# QSPIFlash.net
KiCad netlist of a schematic drawn in Altium Designer
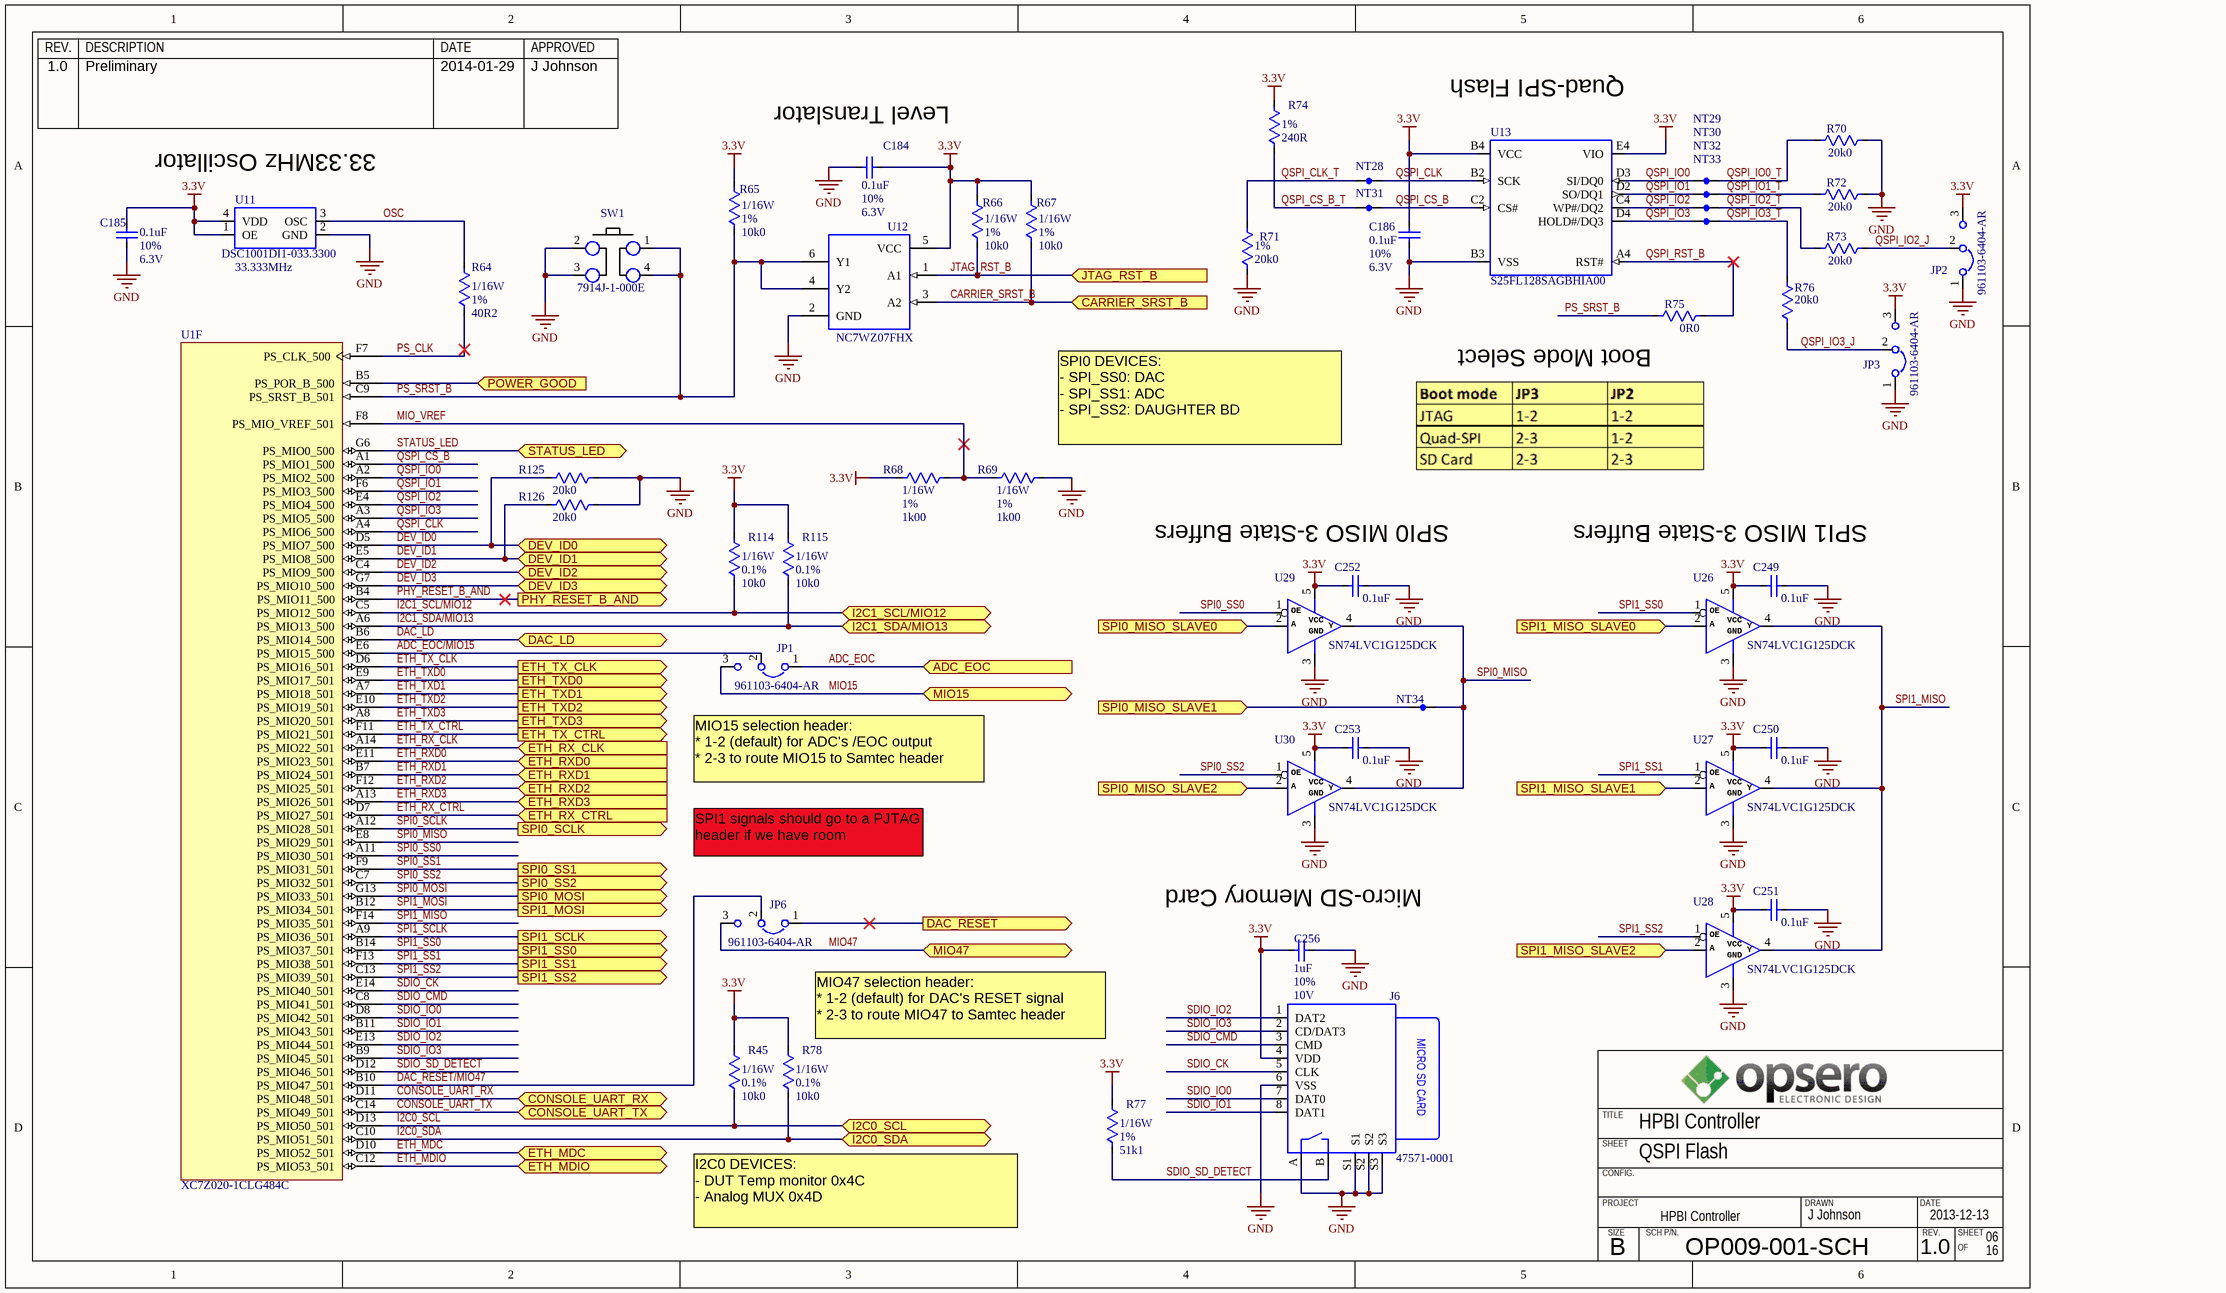
[diagram p0: QSPIFlash.SchDoc]

(export (version "E")
  (design (tool "Eeschema 10.0.6"))
  (components
    (comp (ref "C184")
      (value "0.1uF")
      (footprint "CAPC0603X33N")
      (description "Capacitor ceramic, X5R, 0.1uF, 6.3V, 10%, -55 to +125 C, EIA0201")
      (fields
        (field (name "TOLERANCE") "10%")
        (field (name "VOLTAGE") "6.3V")
        (field (name "Comment") "CAPACITOR_NP_TYPE1")
      )
      (libsource (lib "parts") (part "CAPACITOR_NP_TYPE1"))
    )
    (comp (ref "C185")
      (value "0.1uF")
      (footprint "CAPC0603X33N")
      (description "Capacitor ceramic, X5R, 0.1uF, 6.3V, 10%, -55 to +125 C, EIA0201")
      (fields
        (field (name "TOLERANCE") "10%")
        (field (name "VOLTAGE") "6.3V")
        (field (name "Comment") "CAPACITOR_NP_TYPE1")
      )
      (libsource (lib "parts") (part "CAPACITOR_NP_TYPE1"))
    )
    (comp (ref "C186")
      (value "0.1uF")
      (footprint "CAPC0603X33N")
      (description "Capacitor ceramic, X5R, 0.1uF, 6.3V, 10%, -55 to +125 C, EIA0201")
      (fields
        (field (name "TOLERANCE") "10%")
        (field (name "VOLTAGE") "6.3V")
        (field (name "Comment") "CAPACITOR_NP_TYPE1")
      )
      (libsource (lib "parts") (part "CAPACITOR_NP_TYPE1"))
    )
    (comp (ref "C249")
      (value "0.1uF")
      (footprint "CAPC0603X33N")
      (description "Capacitor ceramic, X5R, 0.1uF, 6.3V, 10%, -55 to +125 C, EIA0201")
      (fields (field (name "TOLERANCE") "10%") (field (name "VOLTAGE") "6.3V"))
      (libsource (lib "parts") (part "CAPACITOR_NP_TYPE1"))
    )
    (comp (ref "C250")
      (value "0.1uF")
      (footprint "CAPC0603X33N")
      (description "Capacitor ceramic, X5R, 0.1uF, 6.3V, 10%, -55 to +125 C, EIA0201")
      (fields (field (name "TOLERANCE") "10%") (field (name "VOLTAGE") "6.3V"))
      (libsource (lib "parts") (part "CAPACITOR_NP_TYPE1"))
    )
    (comp (ref "C251")
      (value "0.1uF")
      (footprint "CAPC0603X33N")
      (description "Capacitor ceramic, X5R, 0.1uF, 6.3V, 10%, -55 to +125 C, EIA0201")
      (fields (field (name "TOLERANCE") "10%") (field (name "VOLTAGE") "6.3V"))
      (libsource (lib "parts") (part "CAPACITOR_NP_TYPE1"))
    )
    (comp (ref "C252")
      (value "0.1uF")
      (footprint "CAPC0603X33N")
      (description "Capacitor ceramic, X5R, 0.1uF, 6.3V, 10%, -55 to +125 C, EIA0201")
      (fields (field (name "TOLERANCE") "10%") (field (name "VOLTAGE") "6.3V"))
      (libsource (lib "parts") (part "CAPACITOR_NP_TYPE1"))
    )
    (comp (ref "C253")
      (value "0.1uF")
      (footprint "CAPC0603X33N")
      (description "Capacitor ceramic, X5R, 0.1uF, 6.3V, 10%, -55 to +125 C, EIA0201")
      (fields (field (name "TOLERANCE") "10%") (field (name "VOLTAGE") "6.3V"))
      (libsource (lib "parts") (part "CAPACITOR_NP_TYPE1"))
    )
    (comp (ref "C256")
      (value "1uF")
      (footprint "CAPC1005X33N")
      (description "Capacitor ceramic, X5R, 1uF, 10V, 10%, -55 to +85 C, EIA0402")
      (fields
        (field (name "TOLERANCE") "10%")
        (field (name "VOLTAGE") "10V")
        (field (name "Comment") "CAPACITOR_NP_TYPE1")
      )
      (libsource (lib "parts") (part "CAPACITOR_NP_TYPE1"))
    )
    (comp (ref "J6")
      (value "SD_MICRO_DET1")
      (footprint "47571-0001")
      (description "MicroSD Card Header with Detect, 9 pin, RA, 1.10 mm, SMT, -40 to +85C")
      (fields
        (field (name "POWER") "Pow")
        (field (name "VOLTAGE") "Vol")
        (field (name "MFG PART NUMBER 1") "47571-0001")
      )
      (libsource (lib "parts") (part "SD_MICRO_DET1"))
    )
    (comp (ref "JP1")
      (value "JP_HDR3x1_DEF1")
      (footprint "JMPR3P254_SHUNT12")
      (description "Jumper Header .100'', 3-pin, Default position 1-2, TH")
      (fields
        (field (name "POWER") "Pow")
        (field (name "VOLTAGE") "Vol")
        (field (name "MFG PART NUMBER 1") "961103-6404-AR")
      )
      (libsource (lib "parts") (part "JP_HDR3x1_DEF1"))
    )
    (comp (ref "JP2")
      (value "JP_HDR3x1_DEF1")
      (footprint "JMPR3P254_SHUNT12")
      (description "Jumper Header .100'', 3-pin, Default position 1-2, TH")
      (fields
        (field (name "POWER") "Pow")
        (field (name "VOLTAGE") "Vol")
        (field (name "MFG PART NUMBER 1") "961103-6404-AR")
      )
      (libsource (lib "") (part "JP_HDR3x1_DEF1_1"))
    )
    (comp (ref "JP3")
      (value "JP_HDR3x1_DEF1")
      (footprint "JMPR3P254_SHUNT12")
      (description "Jumper Header .100'', 3-pin, Default position 1-2, TH")
      (fields
        (field (name "POWER") "Pow")
        (field (name "VOLTAGE") "Vol")
        (field (name "MFG PART NUMBER 1") "961103-6404-AR")
      )
      (libsource (lib "") (part "JP_HDR3x1_DEF1_1"))
    )
    (comp (ref "JP6")
      (value "JP_HDR3x1_DEF1")
      (footprint "JMPR3P254_SHUNT12")
      (description "Jumper Header .100'', 3-pin, Default position 1-2, TH")
      (fields
        (field (name "POWER") "Pow")
        (field (name "VOLTAGE") "Vol")
        (field (name "MFG PART NUMBER 1") "961103-6404-AR")
      )
      (libsource (lib "parts") (part "JP_HDR3x1_DEF1"))
    )
    (comp (ref "NT28")
      (value "NET_TIE_1X1")
      (footprint "NET_TIE_1X1")
      (description "Net Tie 1 to 1")
      (libsource (lib "parts") (part "NET_TIE_1X1"))
    )
    (comp (ref "NT29")
      (value "NET_TIE_1X1")
      (footprint "NET_TIE_1X1")
      (description "Net Tie 1 to 1")
      (libsource (lib "parts") (part "NET_TIE_1X1"))
    )
    (comp (ref "NT30")
      (value "NET_TIE_1X1")
      (footprint "NET_TIE_1X1")
      (description "Net Tie 1 to 1")
      (libsource (lib "parts") (part "NET_TIE_1X1"))
    )
    (comp (ref "NT31")
      (value "NET_TIE_1X1")
      (footprint "NET_TIE_1X1")
      (description "Net Tie 1 to 1")
      (libsource (lib "parts") (part "NET_TIE_1X1"))
    )
    (comp (ref "NT32")
      (value "NET_TIE_1X1")
      (footprint "NET_TIE_1X1")
      (description "Net Tie 1 to 1")
      (libsource (lib "parts") (part "NET_TIE_1X1"))
    )
    (comp (ref "NT33")
      (value "NET_TIE_1X1")
      (footprint "NET_TIE_1X1")
      (description "Net Tie 1 to 1")
      (libsource (lib "parts") (part "NET_TIE_1X1"))
    )
    (comp (ref "NT34")
      (value "NET_TIE_1X1")
      (footprint "NET_TIE_1X1")
      (description "Net Tie 1 to 1")
      (libsource (lib "parts") (part "NET_TIE_1X1"))
    )
    (comp (ref "R45")
      (value "10k0")
      (footprint "RESC1005X33N")
      (description "Resistor, 10k0, 1/16W, 0.1%, -50 to +155 C, EIA0402")
      (fields (field (name "VOLTAGE") "50V") (field (name "POWER") "1/16W") (field (name "TOLERANCE") "0.1%"))
      (libsource (lib "parts") (part "RESISTOR_TYPE1"))
    )
    (comp (ref "R64")
      (value "40R2")
      (footprint "RESC1005X33N")
      (description "Resistor, 40R2, 1/16W, 1%, -50 to +155 C, EIA0402, EIA(M)1005")
      (fields (field (name "VOLTAGE") "50V") (field (name "POWER") "1/16W") (field (name "TOLERANCE") "1%"))
      (libsource (lib "parts") (part "RESISTOR_TYPE1"))
    )
    (comp (ref "R65")
      (value "10k0")
      (footprint "RESC1005X33N")
      (description "Resistor, 10k0, 1/16W, 1%, -55 to +155 C, EIA0402")
      (fields (field (name "VOLTAGE") "50V") (field (name "POWER") "1/16W") (field (name "TOLERANCE") "1%"))
      (libsource (lib "parts") (part "RESISTOR_TYPE1"))
    )
    (comp (ref "R66")
      (value "10k0")
      (footprint "RESC1005X33N")
      (description "Resistor, 10k0, 1/16W, 1%, -55 to +155 C, EIA0402")
      (fields (field (name "VOLTAGE") "50V") (field (name "POWER") "1/16W") (field (name "TOLERANCE") "1%"))
      (libsource (lib "parts") (part "RESISTOR_TYPE1"))
    )
    (comp (ref "R67")
      (value "10k0")
      (footprint "RESC1005X33N")
      (description "Resistor, 10k0, 1/16W, 1%, -55 to +155 C, EIA0402")
      (fields (field (name "VOLTAGE") "50V") (field (name "POWER") "1/16W") (field (name "TOLERANCE") "1%"))
      (libsource (lib "parts") (part "RESISTOR_TYPE1"))
    )
    (comp (ref "R68")
      (value "1k00")
      (footprint "RESC1005X33N")
      (description "Resistor, 1k00, 1/16W, 1%, -55 to +155 C, EIA0402")
      (fields (field (name "VOLTAGE") "50V") (field (name "POWER") "1/16W") (field (name "TOLERANCE") "1%"))
      (libsource (lib "parts") (part "RESISTOR_TYPE1"))
    )
    (comp (ref "R69")
      (value "1k00")
      (footprint "RESC1005X33N")
      (description "Resistor, 1k00, 1/16W, 1%, -55 to +155 C, EIA0402")
      (fields (field (name "VOLTAGE") "50V") (field (name "POWER") "1/16W") (field (name "TOLERANCE") "1%"))
      (libsource (lib "parts") (part "RESISTOR_TYPE1"))
    )
    (comp (ref "R70")
      (value "20k0")
      (footprint "RESC1005X33N")
      (description "Resistor, 20k0, 1/16W, 1%, -50 to +155 C, EIA0402, EIA(M)1005")
      (fields (field (name "VOLTAGE") "50V") (field (name "POWER") "1/16W"))
      (libsource (lib "parts") (part "RESISTOR_TYPE1"))
    )
    (comp (ref "R71")
      (value "20k0")
      (footprint "RESC1005X33N")
      (description "Resistor, 20k0, 1/16W, 1%, -50 to +155 C, EIA0402, EIA(M)1005")
      (fields (field (name "VOLTAGE") "50V") (field (name "POWER") "1/16W") (field (name "TOLERANCE") "1%"))
      (libsource (lib "parts") (part "RESISTOR_TYPE1"))
    )
    (comp (ref "R72")
      (value "20k0")
      (footprint "RESC1005X33N")
      (description "Resistor, 20k0, 1/16W, 1%, -50 to +155 C, EIA0402, EIA(M)1005")
      (fields (field (name "VOLTAGE") "50V") (field (name "POWER") "1/16W"))
      (libsource (lib "parts") (part "RESISTOR_TYPE1"))
    )
    (comp (ref "R73")
      (value "20k0")
      (footprint "RESC1005X33N")
      (description "Resistor, 20k0, 1/16W, 1%, -50 to +155 C, EIA0402, EIA(M)1005")
      (fields (field (name "VOLTAGE") "50V") (field (name "POWER") "1/16W"))
      (libsource (lib "parts") (part "RESISTOR_TYPE1"))
    )
    (comp (ref "R74")
      (value "240R")
      (footprint "RESC1005X33N")
      (description "Resistor, 240R, 1/16W, 1%, -50 to +155 C, EIA0402, EIA(M)1005")
      (fields (field (name "VOLTAGE") "50V") (field (name "POWER") "1/16W") (field (name "TOLERANCE") "1%"))
      (libsource (lib "parts") (part "RESISTOR_TYPE1"))
    )
    (comp (ref "R75")
      (value "0R0")
      (footprint "RESC1005X33N")
      (description "Resistor, 0R0, 1/16W, 1%, -50 to +155 C, EIA0402, EIA(M)1005")
      (fields (field (name "VOLTAGE") "50V") (field (name "POWER") "1/16W"))
      (libsource (lib "parts") (part "RESISTOR_TYPE1"))
    )
    (comp (ref "R76")
      (value "20k0")
      (footprint "RESC1005X33N")
      (description "Resistor, 20k0, 1/16W, 1%, -50 to +155 C, EIA0402, EIA(M)1005")
      (fields (field (name "VOLTAGE") "50V") (field (name "POWER") "1/16W"))
      (libsource (lib "parts") (part "RESISTOR_TYPE1"))
    )
    (comp (ref "R77")
      (value "51k1")
      (footprint "RESC1005X33N")
      (description "Resistor, 51k1, 1/16W, 1%, -50 to +155 C, EIA0402, EIA(M)1005")
      (fields (field (name "VOLTAGE") "50V") (field (name "POWER") "1/16W") (field (name "TOLERANCE") "1%"))
      (libsource (lib "parts") (part "RESISTOR_TYPE1"))
    )
    (comp (ref "R78")
      (value "10k0")
      (footprint "RESC1005X33N")
      (description "Resistor, 10k0, 1/16W, 0.1%, -50 to +155 C, EIA0402")
      (fields (field (name "VOLTAGE") "50V") (field (name "POWER") "1/16W") (field (name "TOLERANCE") "0.1%"))
      (libsource (lib "parts") (part "RESISTOR_TYPE1"))
    )
    (comp (ref "R114")
      (value "10k0")
      (footprint "RESC1005X33N")
      (description "Resistor, 10k0, 1/16W, 0.1%, -50 to +155 C, EIA0402")
      (fields (field (name "VOLTAGE") "50V") (field (name "POWER") "1/16W") (field (name "TOLERANCE") "0.1%"))
      (libsource (lib "parts") (part "RESISTOR_TYPE1"))
    )
    (comp (ref "R115")
      (value "10k0")
      (footprint "RESC1005X33N")
      (description "Resistor, 10k0, 1/16W, 0.1%, -50 to +155 C, EIA0402")
      (fields (field (name "VOLTAGE") "50V") (field (name "POWER") "1/16W") (field (name "TOLERANCE") "0.1%"))
      (libsource (lib "parts") (part "RESISTOR_TYPE1"))
    )
    (comp (ref "R125")
      (value "20k0")
      (footprint "RESC1005X33N")
      (description "Resistor, 20k0, 1/16W, 1%, -50 to +155 C, EIA0402, EIA(M)1005")
      (fields (field (name "VOLTAGE") "50V") (field (name "POWER") "1/16W"))
      (libsource (lib "parts") (part "RESISTOR_TYPE1"))
    )
    (comp (ref "R126")
      (value "20k0")
      (footprint "RESC1005X33N")
      (description "Resistor, 20k0, 1/16W, 1%, -50 to +155 C, EIA0402, EIA(M)1005")
      (fields (field (name "VOLTAGE") "50V") (field (name "POWER") "1/16W"))
      (libsource (lib "parts") (part "RESISTOR_TYPE1"))
    )
    (comp (ref "SW1")
      (value "7914J-1-000E")
      (footprint "7914J-1-000E")
      (description "Switch, tactile, 39V, 4mm, -55 to +125 C, SMD")
      (fields (field (name "POWER") "Pow") (field (name "VOLTAGE") "39V"))
      (libsource (lib "parts") (part "SW_SPST_TYPE1"))
    )
    (comp (ref "U1")
      (value "XC7Z020-1CLG484C")
      (footprint "CLG484")
      (description "667 MHz Zynq™-7000 AP SoC, 130 PS I/O, 200 FPGA I/O, 484-Ball BGA, Speed Grade 1, Commercial Grade")
      (fields (field (name "GENERIC PART NUMBER") "XC7Z020") (field (name "MANUFACTURER") "Xilinx"))
      (libsource (lib "parts") (part "XC7Z020-1CLG484C"))
    )
    (comp (ref "U11")
      (value "33.333MHz")
      (footprint "OSCSC165P200X250X85-4N")
      (description "Oscillator, CMOS, 33.333MHz, 50ppm, 1.7V to 3.6V, -40 to +85C, SMT")
      (fields
        (field (name "VOLTAGE") "1.7V to 3.6V")
        (field (name "MFG PART NUMBER 1") "DSC1001DI1-033.3300")
        (field (name "Comment") "OSCILLATOR_TYPE1")
      )
      (libsource (lib "parts") (part "OSCILLATOR_TYPE1"))
    )
    (comp (ref "U12")
      (value "NC7WZ07FHX")
      (footprint "DFN35P100X100X55-6N")
      (description "UHS Dual Buffer, Tiny Logic, 1.65 to 5.5V, -40 to +85 C, 200mW, MicroPak2-6")
      (fields
        (field (name "POWER") "Pow")
        (field (name "VOLTAGE") "1.65 to 5.5V")
        (field (name "MFG PART NUMBER 1") "NC7WZ07FHX")
      )
      (libsource (lib "parts") (part "NC7WZ07FHX"))
    )
    (comp (ref "U13")
      (value "S25FL128SAGBHIA00")
      (footprint "BGA24C100P5X5_500X500x120")
      (description "SPI Serial FLASH, 128 Mbit, 2.7V to 3.6V,")
      (fields (field (name "POWER") "Pow") (field (name "VOLTAGE") "3.3V"))
      (libsource (lib "parts") (part "S25FL128SAGBHIA00"))
    )
    (comp (ref "U26")
      (value "SN74LVC1G125DCK")
      (footprint "SOT65P210X110-5N")
      (description "Tristate buffer, 1.65 to 5.5V, +/- 24mA, -40 to +125 C, 150mW, SC70")
      (fields (field (name "POWER") "150mW") (field (name "VOLTAGE") "1.65 to 5.5V"))
      (libsource (lib "parts") (part "TINY_SCHM_BUF_TRIS_TYPE1"))
    )
    (comp (ref "U27")
      (value "SN74LVC1G125DCK")
      (footprint "SOT65P210X110-5N")
      (description "Tristate buffer, 1.65 to 5.5V, +/- 24mA, -40 to +125 C, 150mW, SC70")
      (fields (field (name "POWER") "150mW") (field (name "VOLTAGE") "1.65 to 5.5V"))
      (libsource (lib "parts") (part "TINY_SCHM_BUF_TRIS_TYPE1"))
    )
    (comp (ref "U28")
      (value "SN74LVC1G125DCK")
      (footprint "SOT65P210X110-5N")
      (description "Tristate buffer, 1.65 to 5.5V, +/- 24mA, -40 to +125 C, 150mW, SC70")
      (fields (field (name "POWER") "150mW") (field (name "VOLTAGE") "1.65 to 5.5V"))
      (libsource (lib "parts") (part "TINY_SCHM_BUF_TRIS_TYPE1"))
    )
    (comp (ref "U29")
      (value "SN74LVC1G125DCK")
      (footprint "SOT65P210X110-5N")
      (description "Tristate buffer, 1.65 to 5.5V, +/- 24mA, -40 to +125 C, 150mW, SC70")
      (fields (field (name "POWER") "150mW") (field (name "VOLTAGE") "1.65 to 5.5V"))
      (libsource (lib "parts") (part "TINY_SCHM_BUF_TRIS_TYPE1"))
    )
    (comp (ref "U30")
      (value "SN74LVC1G125DCK")
      (footprint "SOT65P210X110-5N")
      (description "Tristate buffer, 1.65 to 5.5V, +/- 24mA, -40 to +125 C, 150mW, SC70")
      (fields (field (name "POWER") "150mW") (field (name "VOLTAGE") "1.65 to 5.5V"))
      (libsource (lib "parts") (part "TINY_SCHM_BUF_TRIS_TYPE1"))
    )
  )
  (nets
    (net (code "1") (name "/ADC_EOC") (class "Default") (node (ref "JP1") (pin "1") (pintype "passive")))
    (net (code "2") (name "/ADC_EOC{slash}MIO15") (class "Default")
      (node (ref "JP1") (pin "2") (pintype "passive"))
      (node (ref "U1") (pin "E6") (pinfunction "PS_MIO15_500_E6") (pintype "bidirectional"))
    )
    (net (code "3") (name "/CARRIER_SRST_B") (class "Default")
      (node (ref "R67") (pin "1") (pinfunction "1_1") (pintype "passive"))
      (node (ref "U12") (pin "3") (pinfunction "A2_3") (pintype "input"))
    )
    (net (code "4") (name "/CONSOLE_UART_RX") (class "Default")
      (node (ref "U1") (pin "D11") (pinfunction "PS_MIO48_501_D11") (pintype "bidirectional"))
    )
    (net (code "5") (name "/CONSOLE_UART_TX") (class "Default")
      (node (ref "U1") (pin "C14") (pinfunction "PS_MIO49_501_C14") (pintype "bidirectional"))
    )
    (net (code "6") (name "/DAC_LD") (class "Default")
      (node (ref "U1") (pin "B6") (pinfunction "PS_MIO14_500_B6") (pintype "bidirectional"))
    )
    (net (code "7") (name "/DAC_RESET") (class "Default") (node (ref "JP6") (pin "1") (pintype "passive")))
    (net (code "8") (name "/DAC_RESET{slash}MIO47") (class "Default")
      (node (ref "JP6") (pin "2") (pintype "passive"))
      (node (ref "U1") (pin "B10") (pinfunction "PS_MIO47_501_B10") (pintype "bidirectional"))
    )
    (net (code "9") (name "/DEV_ID0") (class "Default")
      (node (ref "R125") (pin "1") (pinfunction "1_1") (pintype "passive"))
      (node (ref "U1") (pin "D5") (pinfunction "PS_MIO7_500_D5") (pintype "bidirectional"))
    )
    (net (code "10") (name "/DEV_ID1") (class "Default")
      (node (ref "R126") (pin "1") (pinfunction "1_1") (pintype "passive"))
      (node (ref "U1") (pin "E5") (pinfunction "PS_MIO8_500_E5") (pintype "bidirectional"))
    )
    (net (code "11") (name "/DEV_ID2") (class "Default")
      (node (ref "U1") (pin "C4") (pinfunction "PS_MIO9_500_C4") (pintype "bidirectional"))
    )
    (net (code "12") (name "/DEV_ID3") (class "Default")
      (node (ref "U1") (pin "G7") (pinfunction "PS_MIO10_500_G7") (pintype "bidirectional"))
    )
    (net (code "13") (name "/ETH_MDC") (class "Default")
      (node (ref "U1") (pin "D10") (pinfunction "PS_MIO52_501_D10") (pintype "bidirectional"))
    )
    (net (code "14") (name "/ETH_MDIO") (class "Default")
      (node (ref "U1") (pin "C12") (pinfunction "PS_MIO53_501_C12") (pintype "bidirectional"))
    )
    (net (code "15") (name "/ETH_RXD0") (class "Default")
      (node (ref "U1") (pin "E11") (pinfunction "PS_MIO23_501_E11") (pintype "bidirectional"))
    )
    (net (code "16") (name "/ETH_RXD1") (class "Default")
      (node (ref "U1") (pin "B7") (pinfunction "PS_MIO24_501_B7") (pintype "bidirectional"))
    )
    (net (code "17") (name "/ETH_RXD2") (class "Default")
      (node (ref "U1") (pin "F12") (pinfunction "PS_MIO25_501_F12") (pintype "bidirectional"))
    )
    (net (code "18") (name "/ETH_RXD3") (class "Default")
      (node (ref "U1") (pin "A13") (pinfunction "PS_MIO26_501_A13") (pintype "bidirectional"))
    )
    (net (code "19") (name "/ETH_RX_CLK") (class "Default")
      (node (ref "U1") (pin "A14") (pinfunction "PS_MIO22_501_A14") (pintype "bidirectional"))
    )
    (net (code "20") (name "/ETH_RX_CTRL") (class "Default")
      (node (ref "U1") (pin "D7") (pinfunction "PS_MIO27_501_D7") (pintype "bidirectional"))
    )
    (net (code "21") (name "/ETH_TXD0") (class "Default")
      (node (ref "U1") (pin "E9") (pinfunction "PS_MIO17_501_E9") (pintype "bidirectional"))
    )
    (net (code "22") (name "/ETH_TXD1") (class "Default")
      (node (ref "U1") (pin "A7") (pinfunction "PS_MIO18_501_A7") (pintype "bidirectional"))
    )
    (net (code "23") (name "/ETH_TXD2") (class "Default")
      (node (ref "U1") (pin "E10") (pinfunction "PS_MIO19_501_E10") (pintype "bidirectional"))
    )
    (net (code "24") (name "/ETH_TXD3") (class "Default")
      (node (ref "U1") (pin "A8") (pinfunction "PS_MIO20_501_A8") (pintype "bidirectional"))
    )
    (net (code "25") (name "/ETH_TX_CLK") (class "Default")
      (node (ref "U1") (pin "D6") (pinfunction "PS_MIO16_501_D6") (pintype "bidirectional"))
    )
    (net (code "26") (name "/ETH_TX_CTRL") (class "Default")
      (node (ref "U1") (pin "F11") (pinfunction "PS_MIO21_501_F11") (pintype "bidirectional"))
    )
    (net (code "27") (name "/I2C0_SCL") (class "Default")
      (node (ref "R45") (pin "2") (pinfunction "2_2") (pintype "passive"))
      (node (ref "U1") (pin "D13") (pinfunction "PS_MIO50_501_D13") (pintype "bidirectional"))
    )
    (net (code "28") (name "/I2C0_SDA") (class "Default")
      (node (ref "R78") (pin "2") (pinfunction "2_2") (pintype "passive"))
      (node (ref "U1") (pin "C10") (pinfunction "PS_MIO51_501_C10") (pintype "bidirectional"))
    )
    (net (code "29") (name "/I2C1_SCL{slash}MIO12") (class "Default")
      (node (ref "R114") (pin "2") (pinfunction "2_2") (pintype "passive"))
      (node (ref "U1") (pin "C5") (pinfunction "PS_MIO12_500_C5") (pintype "bidirectional"))
    )
    (net (code "30") (name "/I2C1_SDA{slash}MIO13") (class "Default")
      (node (ref "R115") (pin "2") (pinfunction "2_2") (pintype "passive"))
      (node (ref "U1") (pin "A6") (pinfunction "PS_MIO13_500_A6") (pintype "bidirectional"))
    )
    (net (code "31") (name "/JTAG_RST_B") (class "Default")
      (node (ref "R66") (pin "1") (pinfunction "1_1") (pintype "passive"))
      (node (ref "U12") (pin "1") (pinfunction "A1_1") (pintype "input"))
    )
    (net (code "32") (name "/MIO15") (class "Default") (node (ref "JP1") (pin "3") (pintype "passive")))
    (net (code "33") (name "/MIO47") (class "Default") (node (ref "JP6") (pin "3") (pintype "passive")))
    (net (code "34") (name "/MIO_VREF") (class "Default")
      (node (ref "R68") (pin "2") (pinfunction "2_2") (pintype "passive"))
      (node (ref "R69") (pin "1") (pinfunction "1_1") (pintype "passive"))
      (node (ref "U1") (pin "F8") (pinfunction "PS_MIO_VREF_501_F8") (pintype "input"))
    )
    (net (code "35") (name "/OSC") (class "Default")
      (node (ref "R64") (pin "1") (pinfunction "1_1") (pintype "passive"))
      (node (ref "U11") (pin "3") (pinfunction "OSC_3") (pintype "passive"))
    )
    (net (code "36") (name "/PHY_RESET_B_AND") (class "Default")
      (node (ref "U1") (pin "B4") (pinfunction "PS_MIO11_500_B4") (pintype "bidirectional"))
    )
    (net (code "37") (name "/POWER_GOOD") (class "Default")
      (node (ref "U1") (pin "B5") (pinfunction "PS_POR_B_500_B5") (pintype "input"))
    )
    (net (code "38") (name "/PS_CLK") (class "Default")
      (node (ref "R64") (pin "2") (pinfunction "2_2") (pintype "passive"))
      (node (ref "U1") (pin "F7") (pinfunction "PS_CLK_500_F7") (pintype "input"))
    )
    (net (code "39") (name "/PS_SRST_B") (class "Default")
      (node (ref "R65") (pin "1") (pinfunction "1_1") (pintype "passive"))
      (node (ref "R75") (pin "2") (pinfunction "2_2") (pintype "passive"))
      (node (ref "SW1") (pin "1") (pinfunction "1_1") (pintype "passive"))
      (node (ref "SW1") (pin "4") (pinfunction "4_4") (pintype "passive"))
      (node (ref "U1") (pin "C9") (pinfunction "PS_SRST_B_501_C9") (pintype "input"))
      (node (ref "U12") (pin "4") (pinfunction "Y2_4") (pintype "open_collector"))
      (node (ref "U12") (pin "6") (pinfunction "Y1_6") (pintype "open_collector"))
    )
    (net (code "40") (name "/QSPI_CLK") (class "Default")
      (node (ref "NT28") (pin "2") (pinfunction "2_2") (pintype "passive"))
      (node (ref "U1") (pin "A4") (pinfunction "PS_MIO6_500_A4") (pintype "bidirectional"))
      (node (ref "U13") (pin "B2") (pinfunction "SCK_B2") (pintype "input"))
    )
    (net (code "41") (name "/QSPI_CLK_T") (class "Default")
      (node (ref "NT28") (pin "1") (pinfunction "1_1") (pintype "passive"))
      (node (ref "R71") (pin "2") (pinfunction "2_2") (pintype "passive"))
    )
    (net (code "42") (name "/QSPI_CS_B") (class "Default")
      (node (ref "NT31") (pin "2") (pinfunction "2_2") (pintype "passive"))
      (node (ref "U1") (pin "A1") (pinfunction "PS_MIO1_500_A1") (pintype "bidirectional"))
      (node (ref "U13") (pin "C2") (pinfunction "CS#_C2") (pintype "input"))
    )
    (net (code "43") (name "/QSPI_CS_B_T") (class "Default")
      (node (ref "NT31") (pin "1") (pinfunction "1_1") (pintype "passive"))
      (node (ref "R74") (pin "1") (pinfunction "1_1") (pintype "passive"))
    )
    (net (code "44") (name "/QSPI_IO0") (class "Default")
      (node (ref "NT29") (pin "1") (pinfunction "1_1") (pintype "passive"))
      (node (ref "U1") (pin "A2") (pinfunction "PS_MIO2_500_A2") (pintype "bidirectional"))
      (node (ref "U13") (pin "D3") (pinfunction "SI/DQ0_D3") (pintype "input"))
    )
    (net (code "45") (name "/QSPI_IO0_T") (class "Default")
      (node (ref "NT29") (pin "2") (pinfunction "2_2") (pintype "passive"))
      (node (ref "R70") (pin "2") (pinfunction "2_2") (pintype "passive"))
    )
    (net (code "46") (name "/QSPI_IO1") (class "Default")
      (node (ref "NT30") (pin "1") (pinfunction "1_1") (pintype "passive"))
      (node (ref "U1") (pin "F6") (pinfunction "PS_MIO3_500_F6") (pintype "bidirectional"))
      (node (ref "U13") (pin "D2") (pinfunction "SO/DQ1_D2") (pintype "output"))
    )
    (net (code "47") (name "/QSPI_IO1_T") (class "Default")
      (node (ref "NT30") (pin "2") (pinfunction "2_2") (pintype "passive"))
      (node (ref "R72") (pin "2") (pinfunction "2_2") (pintype "passive"))
    )
    (net (code "48") (name "/QSPI_IO2") (class "Default")
      (node (ref "NT32") (pin "1") (pinfunction "1_1") (pintype "passive"))
      (node (ref "U1") (pin "E4") (pinfunction "PS_MIO4_500_E4") (pintype "bidirectional"))
      (node (ref "U13") (pin "C4") (pinfunction "WP#/DQ2_C4") (pintype "bidirectional"))
    )
    (net (code "49") (name "/QSPI_IO2_J") (class "Default")
      (node (ref "JP2") (pin "2") (pintype "passive"))
      (node (ref "R73") (pin "1") (pinfunction "1_1") (pintype "passive"))
    )
    (net (code "50") (name "/QSPI_IO2_T") (class "Default")
      (node (ref "NT32") (pin "2") (pinfunction "2_2") (pintype "passive"))
      (node (ref "R73") (pin "2") (pinfunction "2_2") (pintype "passive"))
    )
    (net (code "51") (name "/QSPI_IO3") (class "Default")
      (node (ref "NT33") (pin "1") (pinfunction "1_1") (pintype "passive"))
      (node (ref "U1") (pin "A3") (pinfunction "PS_MIO5_500_A3") (pintype "bidirectional"))
      (node (ref "U13") (pin "D4") (pinfunction "HOLD#/DQ3_D4") (pintype "bidirectional"))
    )
    (net (code "52") (name "/QSPI_IO3_J") (class "Default")
      (node (ref "JP3") (pin "2") (pintype "passive"))
      (node (ref "R76") (pin "2") (pinfunction "2_2") (pintype "passive"))
    )
    (net (code "53") (name "/QSPI_IO3_T") (class "Default")
      (node (ref "NT33") (pin "2") (pinfunction "2_2") (pintype "passive"))
      (node (ref "R76") (pin "1") (pinfunction "1_1") (pintype "passive"))
    )
    (net (code "54") (name "/QSPI_RST_B") (class "Default")
      (node (ref "R75") (pin "1") (pinfunction "1_1") (pintype "passive"))
      (node (ref "U13") (pin "A4") (pinfunction "RST#_A4") (pintype "input"))
    )
    (net (code "55") (name "/SDIO_CK") (class "Default")
      (node (ref "J6") (pin "5") (pinfunction "CLK_5") (pintype "passive"))
      (node (ref "U1") (pin "E14") (pinfunction "PS_MIO40_501_E14") (pintype "bidirectional"))
    )
    (net (code "56") (name "/SDIO_CMD") (class "Default")
      (node (ref "J6") (pin "3") (pinfunction "CMD_3") (pintype "passive"))
      (node (ref "U1") (pin "C8") (pinfunction "PS_MIO41_501_C8") (pintype "bidirectional"))
    )
    (net (code "57") (name "/SDIO_IO0") (class "Default")
      (node (ref "J6") (pin "7") (pinfunction "DAT0_7") (pintype "passive"))
      (node (ref "U1") (pin "D8") (pinfunction "PS_MIO42_501_D8") (pintype "bidirectional"))
    )
    (net (code "58") (name "/SDIO_IO1") (class "Default")
      (node (ref "J6") (pin "8") (pinfunction "DAT1_8") (pintype "passive"))
      (node (ref "U1") (pin "B11") (pinfunction "PS_MIO43_501_B11") (pintype "bidirectional"))
    )
    (net (code "59") (name "/SDIO_IO2") (class "Default")
      (node (ref "J6") (pin "1") (pinfunction "DAT2_1") (pintype "passive"))
      (node (ref "U1") (pin "E13") (pinfunction "PS_MIO44_501_E13") (pintype "bidirectional"))
    )
    (net (code "60") (name "/SDIO_IO3") (class "Default")
      (node (ref "J6") (pin "2") (pinfunction "CD/DAT3_2") (pintype "passive"))
      (node (ref "U1") (pin "B9") (pinfunction "PS_MIO45_501_B9") (pintype "bidirectional"))
    )
    (net (code "61") (name "/SDIO_SD_DETECT") (class "Default")
      (node (ref "J6") (pin "B") (pinfunction "B_B") (pintype "passive"))
      (node (ref "R77") (pin "2") (pinfunction "2_2") (pintype "passive"))
      (node (ref "U1") (pin "D12") (pinfunction "PS_MIO46_501_D12") (pintype "bidirectional"))
    )
    (net (code "62") (name "/SPI0_MISO") (class "Default")
      (node (ref "NT34") (pin "2") (pinfunction "2_2") (pintype "passive"))
      (node (ref "U1") (pin "E8") (pinfunction "PS_MIO29_501_E8") (pintype "bidirectional"))
      (node (ref "U29") (pin "4") (pinfunction "Y_4") (pintype "passive"))
      (node (ref "U30") (pin "4") (pinfunction "Y_4") (pintype "passive"))
    )
    (net (code "63") (name "/SPI0_MISO_SLAVE0") (class "Default")
      (node (ref "U29") (pin "2") (pinfunction "A_2") (pintype "passive"))
    )
    (net (code "64") (name "/SPI0_MISO_SLAVE1") (class "Default")
      (node (ref "NT34") (pin "1") (pinfunction "1_1") (pintype "passive"))
    )
    (net (code "65") (name "/SPI0_MISO_SLAVE2") (class "Default")
      (node (ref "U30") (pin "2") (pinfunction "A_2") (pintype "passive"))
    )
    (net (code "66") (name "/SPI0_MOSI") (class "Default")
      (node (ref "U1") (pin "G13") (pinfunction "PS_MIO33_501_G13") (pintype "bidirectional"))
    )
    (net (code "67") (name "/SPI0_SCLK") (class "Default")
      (node (ref "U1") (pin "A12") (pinfunction "PS_MIO28_501_A12") (pintype "bidirectional"))
    )
    (net (code "68") (name "/SPI0_SS0") (class "Default")
      (node (ref "U1") (pin "A11") (pinfunction "PS_MIO30_501_A11") (pintype "bidirectional"))
      (node (ref "U29") (pin "1") (pinfunction "OE_1") (pintype "passive"))
    )
    (net (code "69") (name "/SPI0_SS1") (class "Default")
      (node (ref "U1") (pin "F9") (pinfunction "PS_MIO31_501_F9") (pintype "bidirectional"))
    )
    (net (code "70") (name "/SPI0_SS2") (class "Default")
      (node (ref "U1") (pin "C7") (pinfunction "PS_MIO32_501_C7") (pintype "bidirectional"))
      (node (ref "U30") (pin "1") (pinfunction "OE_1") (pintype "passive"))
    )
    (net (code "71") (name "/SPI1_MISO") (class "Default")
      (node (ref "U1") (pin "F14") (pinfunction "PS_MIO35_501_F14") (pintype "bidirectional"))
      (node (ref "U26") (pin "4") (pinfunction "Y_4") (pintype "passive"))
      (node (ref "U27") (pin "4") (pinfunction "Y_4") (pintype "passive"))
      (node (ref "U28") (pin "4") (pinfunction "Y_4") (pintype "passive"))
    )
    (net (code "72") (name "/SPI1_MISO_SLAVE0") (class "Default")
      (node (ref "U26") (pin "2") (pinfunction "A_2") (pintype "passive"))
    )
    (net (code "73") (name "/SPI1_MISO_SLAVE1") (class "Default")
      (node (ref "U27") (pin "2") (pinfunction "A_2") (pintype "passive"))
    )
    (net (code "74") (name "/SPI1_MISO_SLAVE2") (class "Default")
      (node (ref "U28") (pin "2") (pinfunction "A_2") (pintype "passive"))
    )
    (net (code "75") (name "/SPI1_MOSI") (class "Default")
      (node (ref "U1") (pin "B12") (pinfunction "PS_MIO34_501_B12") (pintype "bidirectional"))
    )
    (net (code "76") (name "/SPI1_SCLK") (class "Default")
      (node (ref "U1") (pin "A9") (pinfunction "PS_MIO36_501_A9") (pintype "bidirectional"))
    )
    (net (code "77") (name "/SPI1_SS0") (class "Default")
      (node (ref "U1") (pin "B14") (pinfunction "PS_MIO37_501_B14") (pintype "bidirectional"))
      (node (ref "U26") (pin "1") (pinfunction "OE_1") (pintype "passive"))
    )
    (net (code "78") (name "/SPI1_SS1") (class "Default")
      (node (ref "U1") (pin "F13") (pinfunction "PS_MIO38_501_F13") (pintype "bidirectional"))
      (node (ref "U27") (pin "1") (pinfunction "OE_1") (pintype "passive"))
    )
    (net (code "79") (name "/SPI1_SS2") (class "Default")
      (node (ref "U1") (pin "C13") (pinfunction "PS_MIO39_501_C13") (pintype "bidirectional"))
      (node (ref "U28") (pin "1") (pinfunction "OE_1") (pintype "passive"))
    )
    (net (code "80") (name "/STATUS_LED") (class "Default")
      (node (ref "U1") (pin "G6") (pinfunction "PS_MIO0_500_G6") (pintype "bidirectional"))
    )
    (net (code "81") (name "3.3V") (class "Default")
      (node (ref "C184") (pin "1") (pinfunction "1_1") (pintype "passive"))
      (node (ref "C185") (pin "1") (pinfunction "1_1") (pintype "passive"))
      (node (ref "C186") (pin "1") (pinfunction "1_1") (pintype "passive"))
      (node (ref "C249") (pin "1") (pinfunction "1_1") (pintype "passive"))
      (node (ref "C250") (pin "1") (pinfunction "1_1") (pintype "passive"))
      (node (ref "C251") (pin "1") (pinfunction "1_1") (pintype "passive"))
      (node (ref "C252") (pin "1") (pinfunction "1_1") (pintype "passive"))
      (node (ref "C253") (pin "1") (pinfunction "1_1") (pintype "passive"))
      (node (ref "C256") (pin "1") (pinfunction "1_1") (pintype "passive"))
      (node (ref "J6") (pin "4") (pinfunction "VDD_4") (pintype "passive"))
      (node (ref "JP2") (pin "3") (pintype "passive"))
      (node (ref "JP3") (pin "3") (pintype "passive"))
      (node (ref "R114") (pin "1") (pinfunction "1_1") (pintype "passive"))
      (node (ref "R115") (pin "1") (pinfunction "1_1") (pintype "passive"))
      (node (ref "R45") (pin "1") (pinfunction "1_1") (pintype "passive"))
      (node (ref "R65") (pin "2") (pinfunction "2_2") (pintype "passive"))
      (node (ref "R66") (pin "2") (pinfunction "2_2") (pintype "passive"))
      (node (ref "R67") (pin "2") (pinfunction "2_2") (pintype "passive"))
      (node (ref "R68") (pin "1") (pinfunction "1_1") (pintype "passive"))
      (node (ref "R74") (pin "2") (pinfunction "2_2") (pintype "passive"))
      (node (ref "R77") (pin "1") (pinfunction "1_1") (pintype "passive"))
      (node (ref "R78") (pin "1") (pinfunction "1_1") (pintype "passive"))
      (node (ref "U11") (pin "1") (pinfunction "OE_1") (pintype "passive"))
      (node (ref "U11") (pin "4") (pinfunction "VDD_4") (pintype "passive"))
      (node (ref "U12") (pin "5") (pinfunction "VCC_5") (pintype "power_in"))
      (node (ref "U13") (pin "B4") (pinfunction "VCC_B4") (pintype "power_in"))
      (node (ref "U13") (pin "E4") (pinfunction "VIO_E4") (pintype "power_in"))
      (node (ref "U26") (pin "5") (pinfunction "VCC_5") (pintype "passive"))
      (node (ref "U27") (pin "5") (pinfunction "VCC_5") (pintype "passive"))
      (node (ref "U28") (pin "5") (pinfunction "VCC_5") (pintype "passive"))
      (node (ref "U29") (pin "5") (pinfunction "VCC_5") (pintype "passive"))
      (node (ref "U30") (pin "5") (pinfunction "VCC_5") (pintype "passive"))
    )
    (net (code "82") (name "GND") (class "Default")
      (node (ref "C184") (pin "2") (pinfunction "2_2") (pintype "passive"))
      (node (ref "C185") (pin "2") (pinfunction "2_2") (pintype "passive"))
      (node (ref "C186") (pin "2") (pinfunction "2_2") (pintype "passive"))
      (node (ref "C249") (pin "2") (pinfunction "2_2") (pintype "passive"))
      (node (ref "C250") (pin "2") (pinfunction "2_2") (pintype "passive"))
      (node (ref "C251") (pin "2") (pinfunction "2_2") (pintype "passive"))
      (node (ref "C252") (pin "2") (pinfunction "2_2") (pintype "passive"))
      (node (ref "C253") (pin "2") (pinfunction "2_2") (pintype "passive"))
      (node (ref "C256") (pin "2") (pinfunction "2_2") (pintype "passive"))
      (node (ref "J6") (pin "6") (pinfunction "VSS_6") (pintype "passive"))
      (node (ref "J6") (pin "A") (pinfunction "A_A") (pintype "passive"))
      (node (ref "J6") (pin "S1") (pinfunction "S1_S1") (pintype "passive"))
      (node (ref "J6") (pin "S2") (pinfunction "S2_S2") (pintype "passive"))
      (node (ref "J6") (pin "S3") (pinfunction "S3_S3") (pintype "passive"))
      (node (ref "JP2") (pin "1") (pintype "passive"))
      (node (ref "JP3") (pin "1") (pintype "passive"))
      (node (ref "R125") (pin "2") (pinfunction "2_2") (pintype "passive"))
      (node (ref "R126") (pin "2") (pinfunction "2_2") (pintype "passive"))
      (node (ref "R69") (pin "2") (pinfunction "2_2") (pintype "passive"))
      (node (ref "R70") (pin "1") (pinfunction "1_1") (pintype "passive"))
      (node (ref "R71") (pin "1") (pinfunction "1_1") (pintype "passive"))
      (node (ref "R72") (pin "1") (pinfunction "1_1") (pintype "passive"))
      (node (ref "SW1") (pin "2") (pinfunction "2_2") (pintype "passive"))
      (node (ref "SW1") (pin "3") (pinfunction "3_3") (pintype "passive"))
      (node (ref "U11") (pin "2") (pinfunction "GND_2") (pintype "passive"))
      (node (ref "U12") (pin "2") (pinfunction "GND_2") (pintype "power_in"))
      (node (ref "U13") (pin "B3") (pinfunction "VSS_B3") (pintype "power_in"))
      (node (ref "U26") (pin "3") (pinfunction "GND_3") (pintype "passive"))
      (node (ref "U27") (pin "3") (pinfunction "GND_3") (pintype "passive"))
      (node (ref "U28") (pin "3") (pinfunction "GND_3") (pintype "passive"))
      (node (ref "U29") (pin "3") (pinfunction "GND_3") (pintype "passive"))
      (node (ref "U30") (pin "3") (pinfunction "GND_3") (pintype "passive"))
    )
  )
)
